# 12v6abuckconverter.net
KiCad netlist of a schematic drawn in EAGLE
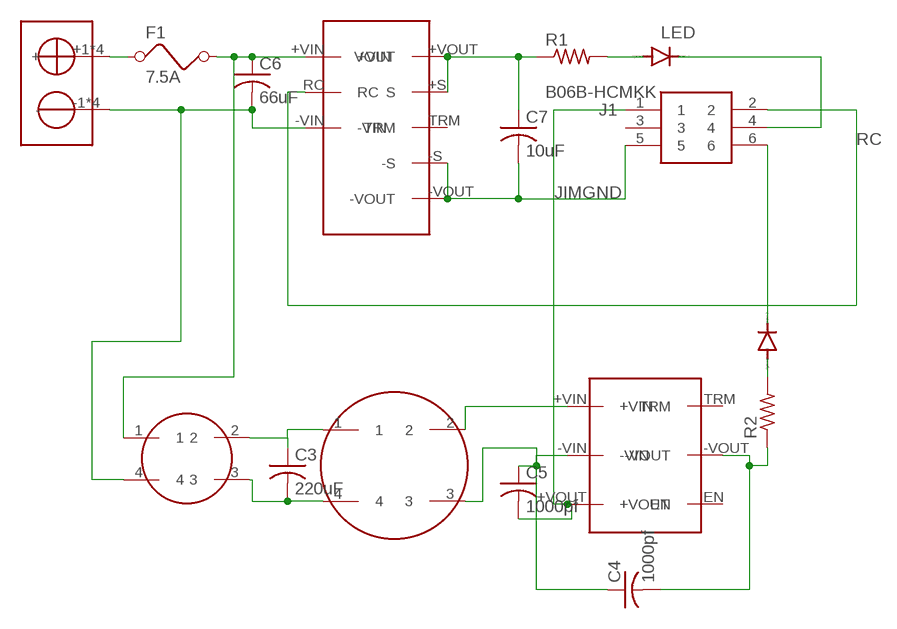
[diagram p0: schematic, sheet 1]

(export (version "E")
  (design (tool "Eeschema 10.0.6"))
  (components
    (comp (ref "BUCK150UH")
      (value "CMNMODECHOKE150UH")
      (footprint "eagle-import:CMNMODECHOKE150UH")
      (libsource (lib "eagle-import") (part "CMNMODECHOKE150UH"))
    )
    (comp (ref "C3")
      (value "220uF")
      (footprint "eagle-import:C0805")
      (libsource (lib "eagle-import") (part "C-USC0805"))
    )
    (comp (ref "C4")
      (value "1000pf")
      (footprint "eagle-import:C0805")
      (libsource (lib "eagle-import") (part "C-USC0805"))
    )
    (comp (ref "C5")
      (value "1000pf")
      (footprint "eagle-import:C0805")
      (libsource (lib "eagle-import") (part "C-USC0805"))
    )
    (comp (ref "C6")
      (value "66uF")
      (footprint "eagle-import:C0805")
      (libsource (lib "eagle-import") (part "C-USC0805"))
    )
    (comp (ref "C7")
      (value "10uF")
      (footprint "eagle-import:C0805")
      (libsource (lib "eagle-import") (part "C-USC0805"))
    )
    (comp (ref "D1")
      (value "BYV95")
      (footprint "eagle-import:SOD57-10")
      (libsource (lib "eagle-import") (part "BYV95"))
    )
    (comp (ref "D2")
      (value "BYV95")
      (footprint "eagle-import:SOD57-10")
      (libsource (lib "eagle-import") (part "BYV95"))
    )
    (comp (ref "F1")
      (value "7.5A")
      (footprint "eagle-import:FUSE")
      (libsource (lib "eagle-import") (part "FUSE"))
    )
    (comp (ref "J1")
      (value "B06B-HCMKK")
      (footprint "eagle-import:B06BHCMKK")
      (fields (field (name "MOUSER_PART_NUMBER") "306-B06B-HCMKK"))
      (libsource (lib "eagle-import") (part "B06B-HCMKK"))
    )
    (comp (ref "R1")
      (value "R-US_R0805")
      (footprint "eagle-import:R0805")
      (libsource (lib "eagle-import") (part "R-US_R0805"))
    )
    (comp (ref "R2")
      (value "R-US_R0805")
      (footprint "eagle-import:R0805")
      (libsource (lib "eagle-import") (part "R-US_R0805"))
    )
    (comp (ref "U$1")
      (value "12V6ABUCKCONVERTER")
      (footprint "eagle-import:12V6ABUCKCONVERTER")
      (libsource (lib "eagle-import") (part "12V6ABUCKCONVERTER"))
    )
    (comp (ref "U$2")
      (value "SB50")
      (footprint "eagle-import:MINI-SB-50")
      (libsource (lib "eagle-import") (part "SB50"))
    )
    (comp (ref "U$3")
      (value "BUCK1.6A")
      (footprint "eagle-import:BUCK1.6A")
      (libsource (lib "eagle-import") (part "BUCK1.6A"))
    )
    (comp (ref "U$4")
      (value "CMNMODECHOKE1.2MH")
      (footprint "eagle-import:CMNMODECHOKE1.2MH")
      (libsource (lib "eagle-import") (part "CMNMODECHOKE1.2MH"))
    )
  )
  (nets
    (net (code "1") (name "/JIMGND") (class "Default")
      (node (ref "C7") (pin "2") (pinfunction "2_2") (pintype "passive"))
      (node (ref "J1") (pin "5") (pinfunction "5_5") (pintype "bidirectional"))
      (node (ref "U$1") (pin "-S") (pinfunction "-S_-S") (pintype "bidirectional"))
      (node (ref "U$1") (pin "-VOUT") (pinfunction "-VOUT_-VOUT") (pintype "bidirectional"))
    )
    (net (code "2") (name "/LED") (class "Default")
      (node (ref "D1") (pin "C") (pinfunction "C_C") (pintype "passive"))
      (node (ref "J1") (pin "4") (pinfunction "4_4") (pintype "bidirectional"))
    )
    (net (code "3") (name "/RC") (class "Default")
      (node (ref "J1") (pin "2") (pinfunction "2_2") (pintype "bidirectional"))
      (node (ref "U$1") (pin "RC") (pinfunction "RC_RC") (pintype "bidirectional"))
    )
    (net (code "4") (name "Net-(BUCK150UH-Pad1)") (class "Default")
      (node (ref "BUCK150UH") (pin "1") (pinfunction "1_1") (pintype "bidirectional"))
      (node (ref "C6") (pin "1") (pinfunction "1_1") (pintype "passive"))
      (node (ref "F1") (pin "2") (pinfunction "2_2") (pintype "passive"))
      (node (ref "U$1") (pin "+VIN") (pinfunction "+VIN_+VIN") (pintype "bidirectional"))
    )
    (net (code "5") (name "Net-(BUCK150UH-Pad2)") (class "Default")
      (node (ref "BUCK150UH") (pin "2") (pinfunction "2_2") (pintype "bidirectional"))
      (node (ref "C3") (pin "1") (pinfunction "1_1") (pintype "passive"))
      (node (ref "U$4") (pin "1") (pinfunction "1_1") (pintype "bidirectional"))
    )
    (net (code "6") (name "Net-(BUCK150UH-Pad3)") (class "Default")
      (node (ref "BUCK150UH") (pin "3") (pinfunction "3_3") (pintype "bidirectional"))
      (node (ref "C3") (pin "2") (pinfunction "2_2") (pintype "passive"))
      (node (ref "U$4") (pin "4") (pinfunction "4_4") (pintype "bidirectional"))
    )
    (net (code "7") (name "Net-(BUCK150UH-Pad4)") (class "Default")
      (node (ref "BUCK150UH") (pin "4") (pinfunction "4_4") (pintype "bidirectional"))
      (node (ref "C6") (pin "2") (pinfunction "2_2") (pintype "passive"))
      (node (ref "U$1") (pin "-VIN") (pinfunction "-VIN_-VIN") (pintype "bidirectional"))
      (node (ref "U$2") (pin "-1") (pinfunction "-_-1") (pintype "bidirectional"))
      (node (ref "U$2") (pin "-2") (pinfunction "-_-2") (pintype "bidirectional"))
      (node (ref "U$2") (pin "-3") (pinfunction "-_-3") (pintype "bidirectional"))
      (node (ref "U$2") (pin "-4") (pinfunction "-_-4") (pintype "bidirectional"))
    )
    (net (code "8") (name "Net-(C4-Pad1)") (class "Default")
      (node (ref "C4") (pin "1") (pinfunction "1_1") (pintype "passive"))
      (node (ref "C5") (pin "1") (pinfunction "1_1") (pintype "passive"))
      (node (ref "U$3") (pin "-VIN") (pinfunction "-VIN_-VIN") (pintype "bidirectional"))
      (node (ref "U$4") (pin "3") (pinfunction "3_3") (pintype "bidirectional"))
    )
    (net (code "9") (name "Net-(C4-Pad2)") (class "Default")
      (node (ref "C4") (pin "2") (pinfunction "2_2") (pintype "passive"))
      (node (ref "R2") (pin "1") (pinfunction "1_1") (pintype "passive"))
      (node (ref "U$3") (pin "-VOUT") (pinfunction "-VOUT_-VOUT") (pintype "bidirectional"))
    )
    (net (code "10") (name "Net-(C5-Pad2)") (class "Default")
      (node (ref "C5") (pin "2") (pinfunction "2_2") (pintype "passive"))
      (node (ref "J1") (pin "1") (pinfunction "1_1") (pintype "bidirectional"))
      (node (ref "U$3") (pin "+VOUT") (pinfunction "+VOUT_+VOUT") (pintype "bidirectional"))
    )
    (net (code "11") (name "Net-(D1-PadA)") (class "Default")
      (node (ref "D1") (pin "A") (pinfunction "A_A") (pintype "passive"))
      (node (ref "R1") (pin "2") (pinfunction "2_2") (pintype "passive"))
    )
    (net (code "12") (name "Net-(D2-PadA)") (class "Default")
      (node (ref "D2") (pin "A") (pinfunction "A_A") (pintype "passive"))
      (node (ref "R2") (pin "2") (pinfunction "2_2") (pintype "passive"))
    )
    (net (code "13") (name "Net-(D2-PadC)") (class "Default")
      (node (ref "D2") (pin "C") (pinfunction "C_C") (pintype "passive"))
      (node (ref "J1") (pin "6") (pinfunction "6_6") (pintype "bidirectional"))
    )
    (net (code "14") (name "Net-(F1-Pad1)") (class "Default")
      (node (ref "F1") (pin "1") (pinfunction "1_1") (pintype "passive"))
      (node (ref "U$2") (pin "+1") (pinfunction "+_+1") (pintype "bidirectional"))
      (node (ref "U$2") (pin "+2") (pinfunction "+_+2") (pintype "bidirectional"))
      (node (ref "U$2") (pin "+3") (pinfunction "+_+3") (pintype "bidirectional"))
      (node (ref "U$2") (pin "+4") (pinfunction "+_+4") (pintype "bidirectional"))
    )
    (net (code "15") (name "Net-(U$1-S)") (class "Default")
      (node (ref "C7") (pin "1") (pinfunction "1_1") (pintype "passive"))
      (node (ref "R1") (pin "1") (pinfunction "1_1") (pintype "passive"))
      (node (ref "U$1") (pin "+S") (pinfunction "S_+S") (pintype "bidirectional"))
      (node (ref "U$1") (pin "+VOUT") (pinfunction "VOUT_+VOUT") (pintype "bidirectional"))
    )
    (net (code "16") (name "Net-(U$3-Pad+VIN)") (class "Default")
      (node (ref "U$3") (pin "+VIN") (pinfunction "+VIN_+VIN") (pintype "bidirectional"))
      (node (ref "U$4") (pin "2") (pinfunction "2_2") (pintype "bidirectional"))
    )
    (net (code "17") (name "unconnected-(J1-Pad3)") (class "Default")
      (node (ref "J1") (pin "3") (pinfunction "3_3") (pintype "bidirectional"))
    )
    (net (code "18") (name "unconnected-(U$1-PadTRM)") (class "Default")
      (node (ref "U$1") (pin "TRM") (pinfunction "TRM_TRM") (pintype "bidirectional"))
    )
    (net (code "19") (name "unconnected-(U$3-PadEN)") (class "Default")
      (node (ref "U$3") (pin "EN") (pinfunction "EN_EN") (pintype "bidirectional"))
    )
    (net (code "20") (name "unconnected-(U$3-PadTRM)") (class "Default")
      (node (ref "U$3") (pin "TRM") (pinfunction "TRM_TRM") (pintype "bidirectional"))
    )
  )
)
